# design.net
KiCad netlist of a schematic drawn in EasyEDA Pro
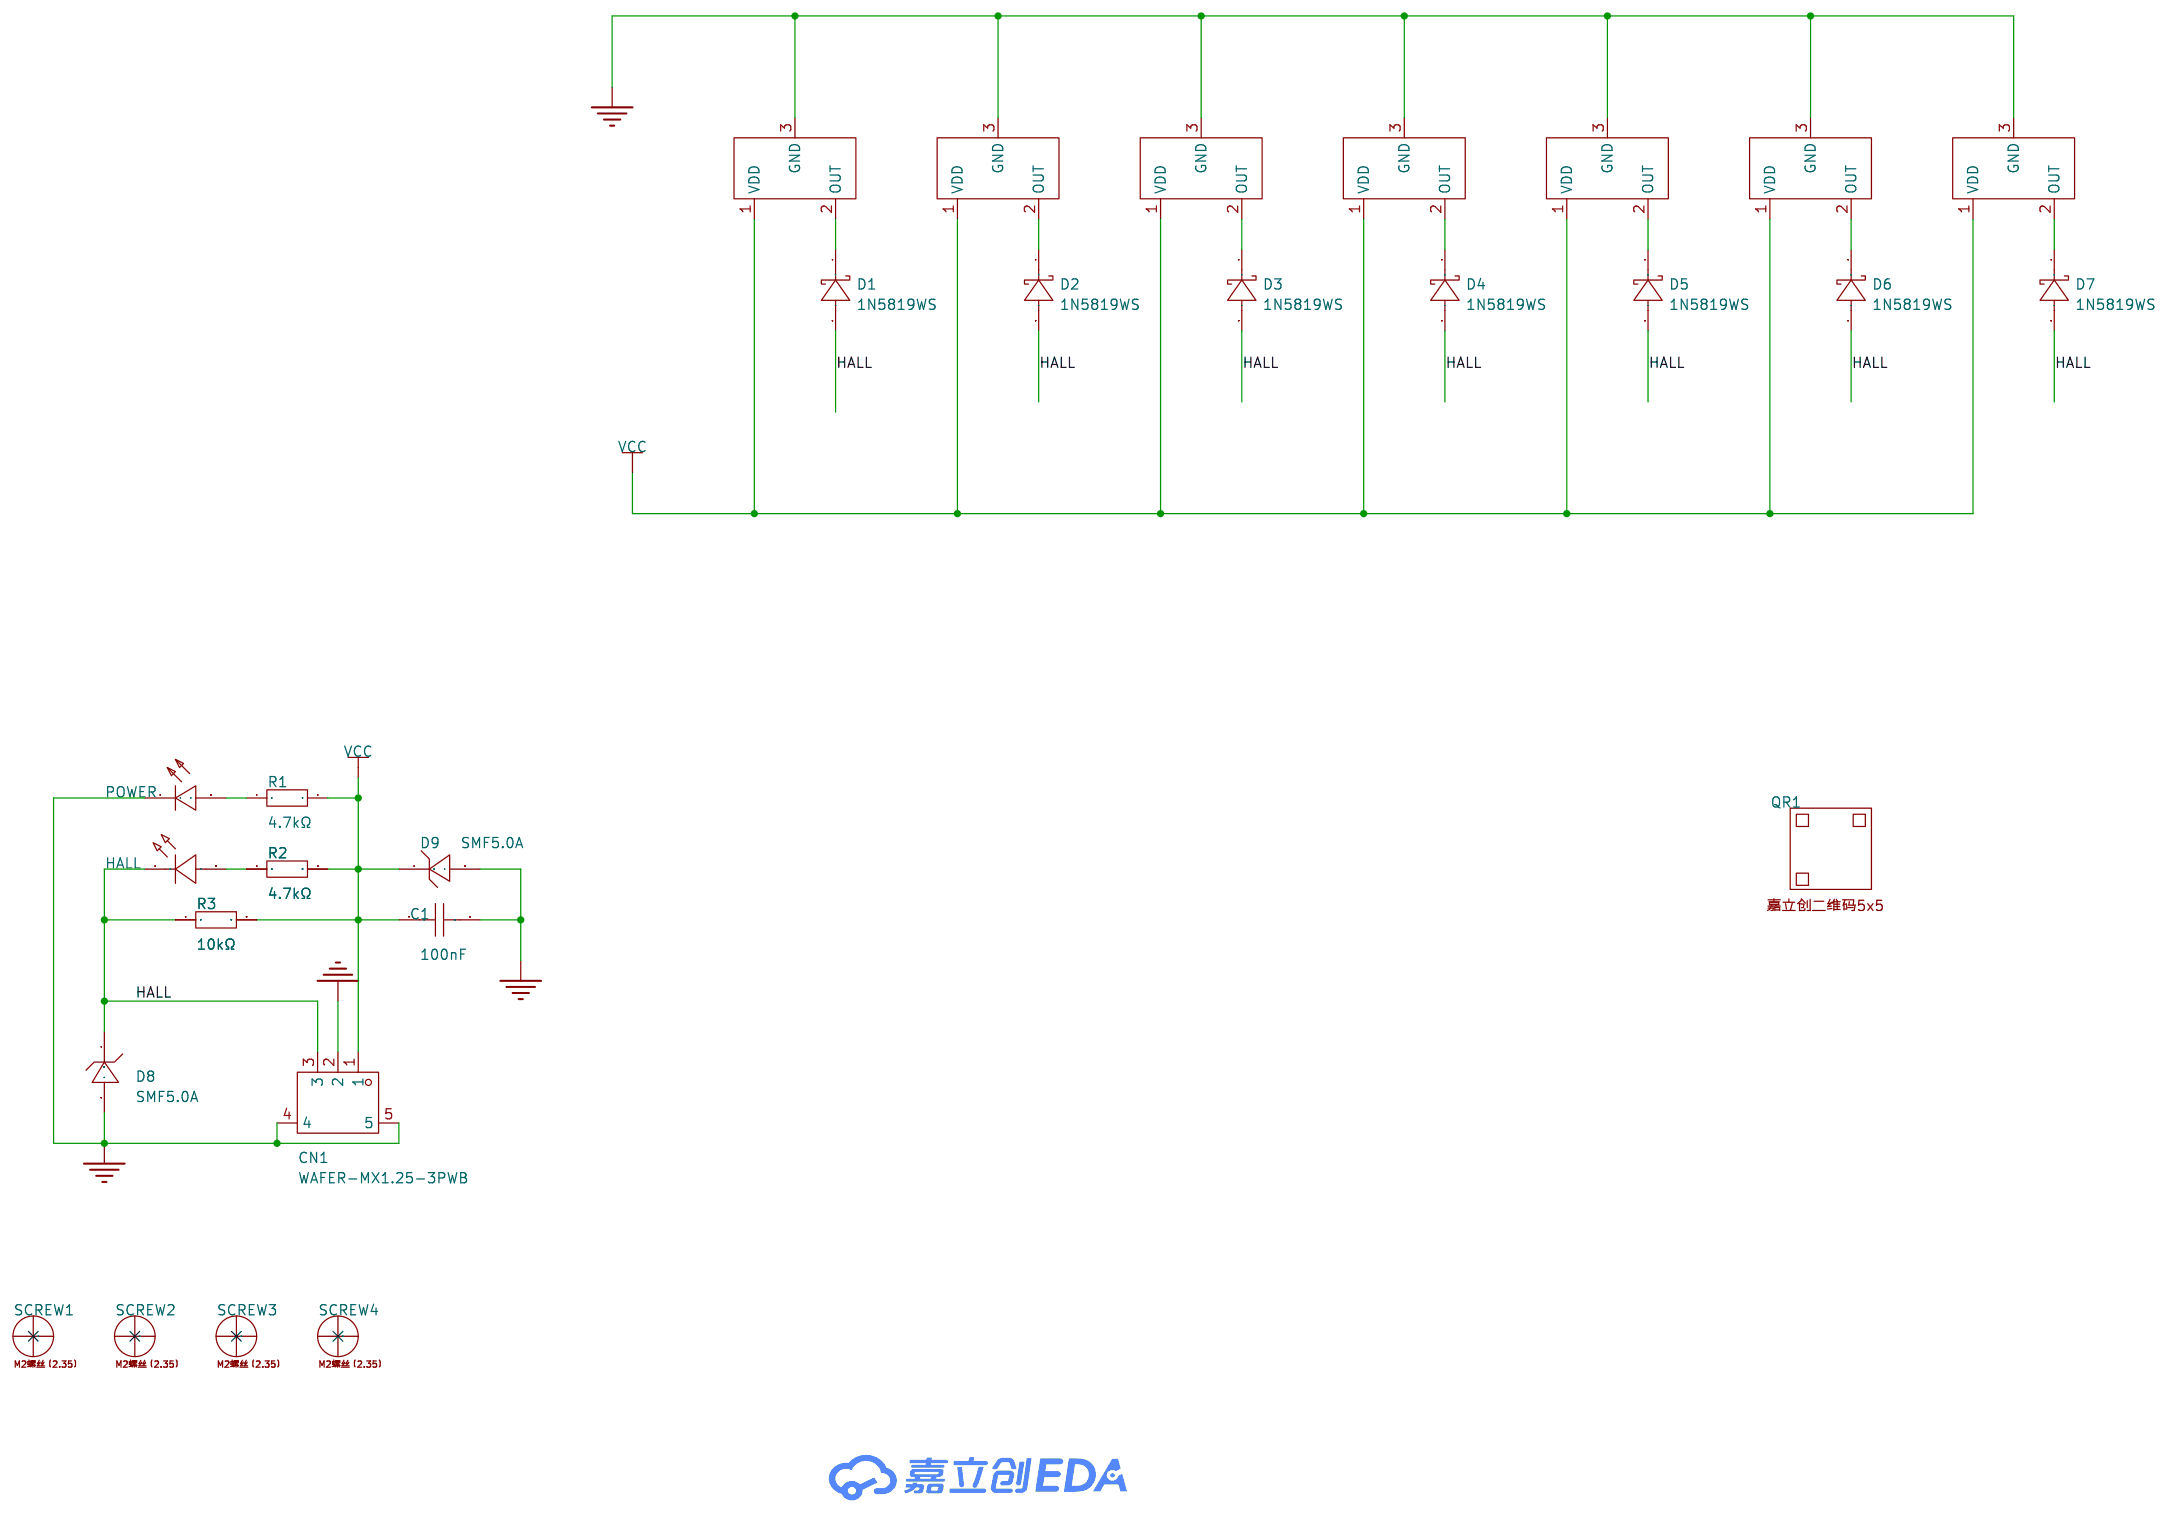
[diagram p0: schematic sheet]

(export (version "E")
  (design (tool "Eeschema 10.0.6"))
  (components
    (comp (ref "C1")
      (value "100nF")
      (footprint "easyedapro:C0805")
      (description "容值:100nF;精度:±10%;额定电压:50V;材质(温度系数):X7R;")
      (fields
        (field (name "Manufacturer Part") "CC0805KRX7R9BB104")
        (field (name "Manufacturer") "YAGEO(国巨)")
      )
      (libsource (lib "easyedapro") (part "CC0805KRX7R9BB104"))
    )
    (comp (ref "CN1")
      (value "WAFER-MX1.25-3PWB")
      (footprint "easyedapro:CONN-SMD_3P-P1.25_WAFER-MX1.25-3PWB")
      (fields (field (name "Manufacturer") "XUNPU(讯普)"))
      (libsource (lib "easyedapro") (part "WAFER-MX1.25-3PWB"))
    )
    (comp (ref "D1")
      (value "1N5819WS")
      (footprint "easyedapro:SOD-323_L1.6-W1.3-LS2.6-RD-1")
      (description "正向压降(Vf):580mV@1A;直流反向耐压(Vr):40V;整流电流:1A;")
      (fields (field (name "Manufacturer") "GOODWORK(固得沃克)"))
      (libsource (lib "easyedapro") (part "1N5819WS_C2903903"))
    )
    (comp (ref "D2")
      (value "1N5819WS")
      (footprint "easyedapro:SOD-323_L1.6-W1.3-LS2.6-RD-1")
      (description "正向压降(Vf):580mV@1A;直流反向耐压(Vr):40V;整流电流:1A;")
      (fields (field (name "Manufacturer") "GOODWORK(固得沃克)"))
      (libsource (lib "easyedapro") (part "1N5819WS_C2903903"))
    )
    (comp (ref "D3")
      (value "1N5819WS")
      (footprint "easyedapro:SOD-323_L1.6-W1.3-LS2.6-RD-1")
      (description "正向压降(Vf):580mV@1A;直流反向耐压(Vr):40V;整流电流:1A;")
      (fields (field (name "Manufacturer") "GOODWORK(固得沃克)"))
      (libsource (lib "easyedapro") (part "1N5819WS_C2903903"))
    )
    (comp (ref "D4")
      (value "1N5819WS")
      (footprint "easyedapro:SOD-323_L1.6-W1.3-LS2.6-RD-1")
      (description "正向压降(Vf):580mV@1A;直流反向耐压(Vr):40V;整流电流:1A;")
      (fields (field (name "Manufacturer") "GOODWORK(固得沃克)"))
      (libsource (lib "easyedapro") (part "1N5819WS_C2903903"))
    )
    (comp (ref "D5")
      (value "1N5819WS")
      (footprint "easyedapro:SOD-323_L1.6-W1.3-LS2.6-RD-1")
      (description "正向压降(Vf):580mV@1A;直流反向耐压(Vr):40V;整流电流:1A;")
      (fields (field (name "Manufacturer") "GOODWORK(固得沃克)"))
      (libsource (lib "easyedapro") (part "1N5819WS_C2903903"))
    )
    (comp (ref "D6")
      (value "1N5819WS")
      (footprint "easyedapro:SOD-323_L1.6-W1.3-LS2.6-RD-1")
      (description "正向压降(Vf):580mV@1A;直流反向耐压(Vr):40V;整流电流:1A;")
      (fields (field (name "Manufacturer") "GOODWORK(固得沃克)"))
      (libsource (lib "easyedapro") (part "1N5819WS_C2903903"))
    )
    (comp (ref "D7")
      (value "1N5819WS")
      (footprint "easyedapro:SOD-323_L1.6-W1.3-LS2.6-RD-1")
      (description "正向压降(Vf):580mV@1A;直流反向耐压(Vr):40V;整流电流:1A;")
      (fields (field (name "Manufacturer") "GOODWORK(固得沃克)"))
      (libsource (lib "easyedapro") (part "1N5819WS_C2903903"))
    )
    (comp (ref "D8")
      (value "SMF5.0A")
      (footprint "easyedapro:SOD-123FL_L2.7-W1.8-LS3.8-RD")
      (description "反向截止电压(Vrwm):5V;最大钳位电压:9.2V;峰值脉冲电流(Ipp)@10/1000us:21.7A;击穿电压:6.4V;")
      (fields (field (name "Manufacturer") "MDD"))
      (libsource (lib "easyedapro") (part "SMF5.0A_C193402"))
    )
    (comp (ref "D9")
      (value "SMF5.0A")
      (footprint "easyedapro:SOD-123FL_L2.7-W1.8-LS3.8-RD")
      (description "反向截止电压(Vrwm):5V;最大钳位电压:9.2V;峰值脉冲电流(Ipp)@10/1000us:21.7A;击穿电压:6.4V;")
      (fields (field (name "Manufacturer") "MDD"))
      (libsource (lib "easyedapro") (part "SMF5.0A_C193402"))
    )
    (comp (ref "HALL")
      (value "XL-2012SYGC")
      (footprint "easyedapro:LED0805-RD_GREEN")
      (fields (field (name "Manufacturer") "XINGLIGHT(成兴光)"))
      (libsource (lib "easyedapro") (part "XL-2012SYGC"))
    )
    (comp (ref "POWER")
      (value "NCD0603R1")
      (footprint "easyedapro:LED0603-RD_RED")
      (fields (field (name "Manufacturer") "国星光电"))
      (libsource (lib "easyedapro") (part "FC-DA1608HRK-620D"))
    )
    (comp (ref "QR1")
      (value "~")
      (footprint "easyedapro:JLC-QRCODE-5x5")
      (libsource (lib "easyedapro") (part "嘉立创二维码5x5"))
    )
    (comp (ref "R1")
      (value "4.7kΩ")
      (footprint "easyedapro:R0805")
      (description "电阻类型:厚膜电阻;阻值:4.7kΩ;精度:±1%;功率:125mW;最大工作电压:150V;温度系数:±100ppm/°C;")
      (fields
        (field (name "Manufacturer Part") "0805W8F4701T5E")
        (field (name "Manufacturer") "UNI-ROYAL(厚声)")
      )
      (libsource (lib "easyedapro") (part "0805W8F4701T5E"))
    )
    (comp (ref "R2")
      (value "4.7kΩ")
      (footprint "easyedapro:R0805")
      (description "电阻类型:厚膜电阻;阻值:4.7kΩ;精度:±1%;功率:125mW;最大工作电压:150V;温度系数:±100ppm/°C;")
      (fields
        (field (name "Manufacturer Part") "0805W8F4701T5E")
        (field (name "Manufacturer") "UNI-ROYAL(厚声)")
      )
      (libsource (lib "easyedapro") (part "0805W8F4701T5E"))
    )
    (comp (ref "R3")
      (value "10kΩ")
      (footprint "easyedapro:R0805")
      (description "电阻类型:厚膜电阻;阻值:10kΩ;精度:±1%;功率:125mW;最大工作电压:150V;温度系数:±100ppm/°C;")
      (fields
        (field (name "Manufacturer Part") "0805W8F1002T5E")
        (field (name "Manufacturer") "UNI-ROYAL(厚声)")
      )
      (libsource (lib "easyedapro") (part "0805W8F1002T5E"))
    )
    (comp (ref "SCREW1")
      (value "~")
      (footprint "easyedapro:M2螺丝（2.35）")
      (libsource (lib "easyedapro") (part "M2螺丝（2.35）"))
    )
    (comp (ref "SCREW2")
      (value "~")
      (footprint "easyedapro:M2螺丝（2.35）")
      (libsource (lib "easyedapro") (part "M2螺丝（2.35）"))
    )
    (comp (ref "SCREW3")
      (value "~")
      (footprint "easyedapro:M2螺丝（2.35）")
      (libsource (lib "easyedapro") (part "M2螺丝（2.35）"))
    )
    (comp (ref "SCREW4")
      (value "~")
      (footprint "easyedapro:M2螺丝（2.35）")
      (libsource (lib "easyedapro") (part "M2螺丝（2.35）"))
    )
    (comp (ref "U1")
      (value "~")
      (footprint "easyedapro:SOT-23_L2.9-W1.3-P0.95-LS2.4-TL")
      (libsource (lib "easyedapro") (part "霍尔DH553"))
    )
    (comp (ref "U2")
      (value "~")
      (footprint "easyedapro:SOT-23_L2.9-W1.3-P0.95-LS2.4-TL")
      (libsource (lib "easyedapro") (part "霍尔DH553"))
    )
    (comp (ref "U3")
      (value "~")
      (footprint "easyedapro:SOT-23_L2.9-W1.3-P0.95-LS2.4-TL")
      (libsource (lib "easyedapro") (part "霍尔DH553"))
    )
    (comp (ref "U4")
      (value "~")
      (footprint "easyedapro:SOT-23_L2.9-W1.3-P0.95-LS2.4-TL")
      (libsource (lib "easyedapro") (part "霍尔DH553"))
    )
    (comp (ref "U5")
      (value "~")
      (footprint "easyedapro:SOT-23_L2.9-W1.3-P0.95-LS2.4-TL")
      (libsource (lib "easyedapro") (part "霍尔DH553"))
    )
    (comp (ref "U6")
      (value "~")
      (footprint "easyedapro:SOT-23_L2.9-W1.3-P0.95-LS2.4-TL")
      (libsource (lib "easyedapro") (part "霍尔DH553"))
    )
    (comp (ref "U7")
      (value "~")
      (footprint "easyedapro:SOT-23_L2.9-W1.3-P0.95-LS2.4-TL")
      (libsource (lib "easyedapro") (part "霍尔DH553"))
    )
  )
  (nets
    (net (code "1") (name "/HALL") (class "Default")
      (node (ref "CN1") (pin "3") (pinfunction "3_3") (pintype "unspecified"))
      (node (ref "D1") (pin "2") (pinfunction "A_2") (pintype "unspecified"))
      (node (ref "D2") (pin "2") (pinfunction "A_2") (pintype "unspecified"))
      (node (ref "D3") (pin "2") (pinfunction "A_2") (pintype "unspecified"))
      (node (ref "D4") (pin "2") (pinfunction "A_2") (pintype "unspecified"))
      (node (ref "D5") (pin "2") (pinfunction "A_2") (pintype "unspecified"))
      (node (ref "D6") (pin "2") (pinfunction "A_2") (pintype "unspecified"))
      (node (ref "D7") (pin "2") (pinfunction "A_2") (pintype "unspecified"))
      (node (ref "D8") (pin "1") (pinfunction "C_1") (pintype "unspecified"))
      (node (ref "HALL") (pin "1") (pinfunction "K_1") (pintype "unspecified"))
      (node (ref "R3") (pin "1") (pinfunction "1_1") (pintype "input"))
    )
    (net (code "2") (name "GND") (class "Default")
      (node (ref "C1") (pin "2") (pinfunction "2_2") (pintype "unspecified"))
      (node (ref "CN1") (pin "2") (pinfunction "2_2") (pintype "unspecified"))
      (node (ref "CN1") (pin "4") (pinfunction "4_4") (pintype "unspecified"))
      (node (ref "CN1") (pin "5") (pinfunction "5_5") (pintype "unspecified"))
      (node (ref "D8") (pin "2") (pinfunction "A_2") (pintype "unspecified"))
      (node (ref "D9") (pin "2") (pinfunction "A_2") (pintype "unspecified"))
      (node (ref "POWER") (pin "1") (pinfunction "K_1") (pintype "input"))
      (node (ref "U1") (pin "3") (pinfunction "GND_3") (pintype "input"))
      (node (ref "U2") (pin "3") (pinfunction "GND_3") (pintype "input"))
      (node (ref "U3") (pin "3") (pinfunction "GND_3") (pintype "input"))
      (node (ref "U4") (pin "3") (pinfunction "GND_3") (pintype "input"))
      (node (ref "U5") (pin "3") (pinfunction "GND_3") (pintype "input"))
      (node (ref "U6") (pin "3") (pinfunction "GND_3") (pintype "input"))
      (node (ref "U7") (pin "3") (pinfunction "GND_3") (pintype "input"))
    )
    (net (code "3") (name "Net-(D1-K)") (class "Default")
      (node (ref "D1") (pin "1") (pinfunction "K_1") (pintype "unspecified"))
      (node (ref "U1") (pin "2") (pinfunction "OUT_2") (pintype "output"))
    )
    (net (code "4") (name "Net-(D2-K)") (class "Default")
      (node (ref "D2") (pin "1") (pinfunction "K_1") (pintype "unspecified"))
      (node (ref "U2") (pin "2") (pinfunction "OUT_2") (pintype "output"))
    )
    (net (code "5") (name "Net-(D3-K)") (class "Default")
      (node (ref "D3") (pin "1") (pinfunction "K_1") (pintype "unspecified"))
      (node (ref "U3") (pin "2") (pinfunction "OUT_2") (pintype "output"))
    )
    (net (code "6") (name "Net-(D4-K)") (class "Default")
      (node (ref "D4") (pin "1") (pinfunction "K_1") (pintype "unspecified"))
      (node (ref "U4") (pin "2") (pinfunction "OUT_2") (pintype "output"))
    )
    (net (code "7") (name "Net-(D5-K)") (class "Default")
      (node (ref "D5") (pin "1") (pinfunction "K_1") (pintype "unspecified"))
      (node (ref "U5") (pin "2") (pinfunction "OUT_2") (pintype "output"))
    )
    (net (code "8") (name "Net-(D6-K)") (class "Default")
      (node (ref "D6") (pin "1") (pinfunction "K_1") (pintype "unspecified"))
      (node (ref "U6") (pin "2") (pinfunction "OUT_2") (pintype "output"))
    )
    (net (code "9") (name "Net-(D7-K)") (class "Default")
      (node (ref "D7") (pin "1") (pinfunction "K_1") (pintype "unspecified"))
      (node (ref "U7") (pin "2") (pinfunction "OUT_2") (pintype "output"))
    )
    (net (code "10") (name "Net-(HALL-A)") (class "Default")
      (node (ref "HALL") (pin "2") (pinfunction "A_2") (pintype "unspecified"))
      (node (ref "R2") (pin "1") (pinfunction "1_1") (pintype "input"))
    )
    (net (code "11") (name "Net-(POWER-A)") (class "Default")
      (node (ref "POWER") (pin "2") (pinfunction "A_2") (pintype "input"))
      (node (ref "R1") (pin "1") (pinfunction "1_1") (pintype "input"))
    )
    (net (code "12") (name "VCC") (class "Default")
      (node (ref "C1") (pin "1") (pinfunction "1_1") (pintype "unspecified"))
      (node (ref "CN1") (pin "1") (pinfunction "1_1") (pintype "unspecified"))
      (node (ref "D9") (pin "1") (pinfunction "C_1") (pintype "unspecified"))
      (node (ref "R1") (pin "2") (pinfunction "2_2") (pintype "input"))
      (node (ref "R2") (pin "2") (pinfunction "2_2") (pintype "input"))
      (node (ref "R3") (pin "2") (pinfunction "2_2") (pintype "input"))
      (node (ref "U1") (pin "1") (pinfunction "VDD_1") (pintype "input"))
      (node (ref "U2") (pin "1") (pinfunction "VDD_1") (pintype "input"))
      (node (ref "U3") (pin "1") (pinfunction "VDD_1") (pintype "input"))
      (node (ref "U4") (pin "1") (pinfunction "VDD_1") (pintype "input"))
      (node (ref "U5") (pin "1") (pinfunction "VDD_1") (pintype "input"))
      (node (ref "U6") (pin "1") (pinfunction "VDD_1") (pintype "input"))
      (node (ref "U7") (pin "1") (pinfunction "VDD_1") (pintype "input"))
    )
    (net (code "13") (name "unconnected-(SCREW1-Pad1)") (class "Default")
      (node (ref "SCREW1") (pin "1") (pinfunction "1_1") (pintype "input+no_connect"))
    )
    (net (code "14") (name "unconnected-(SCREW2-Pad1)") (class "Default")
      (node (ref "SCREW2") (pin "1") (pinfunction "1_1") (pintype "input+no_connect"))
    )
    (net (code "15") (name "unconnected-(SCREW3-Pad1)") (class "Default")
      (node (ref "SCREW3") (pin "1") (pinfunction "1_1") (pintype "input+no_connect"))
    )
    (net (code "16") (name "unconnected-(SCREW4-Pad1)") (class "Default")
      (node (ref "SCREW4") (pin "1") (pinfunction "1_1") (pintype "input+no_connect"))
    )
  )
)
